# Buttons.net
KiCad netlist of a schematic drawn in Altium Designer
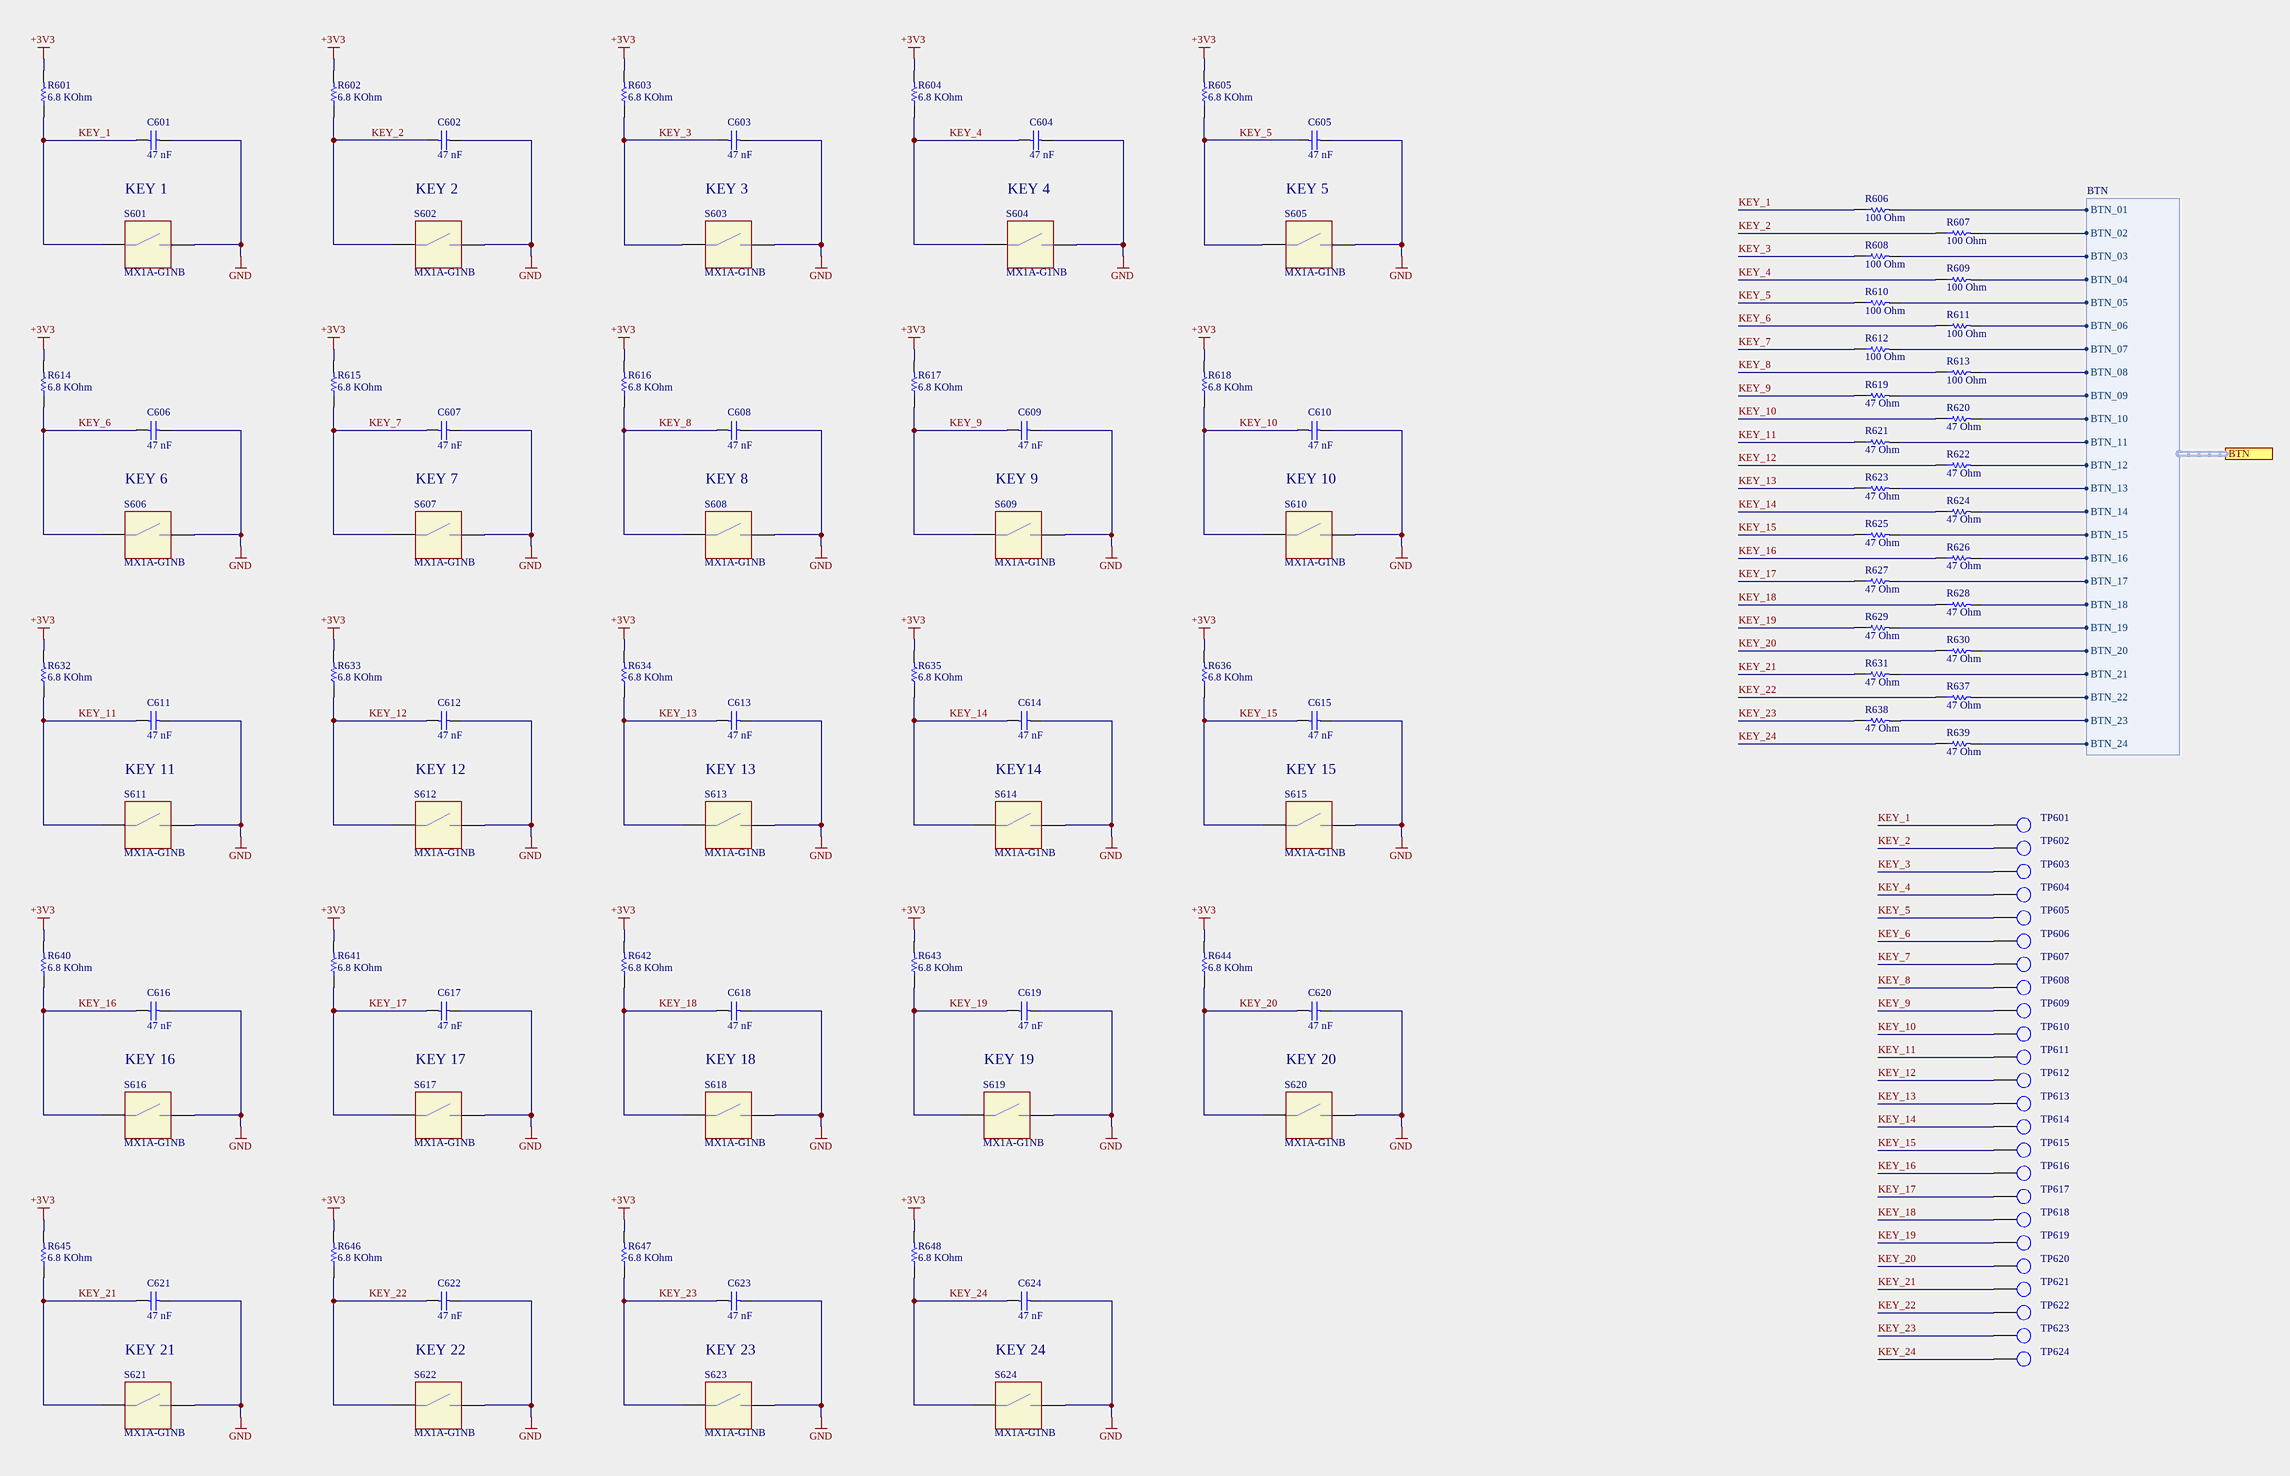
[diagram p0: Buttons.SchDoc]

(export (version "E")
  (design (tool "Eeschema 10.0.6"))
  (components
    (comp (ref "C601")
      (value "CAP-47N")
      (footprint "CAPC0603")
      (description "Chip Capacitor, 47 nF, +/- 5%")
      (fields (field (name "TOLERANCE") "5 %") (field (name "CAPACITANCE") "47 nF"))
      (libsource (lib "Конденсаторы керамические SMD") (part "CAP-47N"))
    )
    (comp (ref "C602")
      (value "CAP-47N")
      (footprint "CAPC0603")
      (description "Chip Capacitor, 47 nF, +/- 5%")
      (fields (field (name "TOLERANCE") "5 %") (field (name "CAPACITANCE") "47 nF"))
      (libsource (lib "Конденсаторы керамические SMD") (part "CAP-47N"))
    )
    (comp (ref "C603")
      (value "CAP-47N")
      (footprint "CAPC0603")
      (description "Chip Capacitor, 47 nF, +/- 5%")
      (fields (field (name "TOLERANCE") "5 %") (field (name "CAPACITANCE") "47 nF"))
      (libsource (lib "Конденсаторы керамические SMD") (part "CAP-47N"))
    )
    (comp (ref "C604")
      (value "CAP-47N")
      (footprint "CAPC0603")
      (description "Chip Capacitor, 47 nF, +/- 5%")
      (fields (field (name "TOLERANCE") "5 %") (field (name "CAPACITANCE") "47 nF"))
      (libsource (lib "Конденсаторы керамические SMD") (part "CAP-47N"))
    )
    (comp (ref "C605")
      (value "CAP-47N")
      (footprint "CAPC0603")
      (description "Chip Capacitor, 47 nF, +/- 5%")
      (fields (field (name "TOLERANCE") "5 %") (field (name "CAPACITANCE") "47 nF"))
      (libsource (lib "Конденсаторы керамические SMD") (part "CAP-47N"))
    )
    (comp (ref "C606")
      (value "CAP-47N")
      (footprint "CAPC0603")
      (description "Chip Capacitor, 47 nF, +/- 5%")
      (fields (field (name "TOLERANCE") "5 %") (field (name "CAPACITANCE") "47 nF"))
      (libsource (lib "Конденсаторы керамические SMD") (part "CAP-47N"))
    )
    (comp (ref "C607")
      (value "CAP-47N")
      (footprint "CAPC0603")
      (description "Chip Capacitor, 47 nF, +/- 5%")
      (fields (field (name "TOLERANCE") "5 %") (field (name "CAPACITANCE") "47 nF"))
      (libsource (lib "Конденсаторы керамические SMD") (part "CAP-47N"))
    )
    (comp (ref "C608")
      (value "CAP-47N")
      (footprint "CAPC0603")
      (description "Chip Capacitor, 47 nF, +/- 5%")
      (fields (field (name "TOLERANCE") "5 %") (field (name "CAPACITANCE") "47 nF"))
      (libsource (lib "Конденсаторы керамические SMD") (part "CAP-47N"))
    )
    (comp (ref "C609")
      (value "CAP-47N")
      (footprint "CAPC0603")
      (description "Chip Capacitor, 47 nF, +/- 5%")
      (fields (field (name "TOLERANCE") "5 %") (field (name "CAPACITANCE") "47 nF"))
      (libsource (lib "Конденсаторы керамические SMD") (part "CAP-47N"))
    )
    (comp (ref "C610")
      (value "CAP-47N")
      (footprint "CAPC0603")
      (description "Chip Capacitor, 47 nF, +/- 5%")
      (fields (field (name "TOLERANCE") "5 %") (field (name "CAPACITANCE") "47 nF"))
      (libsource (lib "Конденсаторы керамические SMD") (part "CAP-47N"))
    )
    (comp (ref "C611")
      (value "CAP-47N")
      (footprint "CAPC0603")
      (description "Chip Capacitor, 47 nF, +/- 5%")
      (fields (field (name "TOLERANCE") "5 %") (field (name "CAPACITANCE") "47 nF"))
      (libsource (lib "Конденсаторы керамические SMD") (part "CAP-47N"))
    )
    (comp (ref "C612")
      (value "CAP-47N")
      (footprint "CAPC0603")
      (description "Chip Capacitor, 47 nF, +/- 5%")
      (fields (field (name "TOLERANCE") "5 %") (field (name "CAPACITANCE") "47 nF"))
      (libsource (lib "Конденсаторы керамические SMD") (part "CAP-47N"))
    )
    (comp (ref "C613")
      (value "CAP-47N")
      (footprint "CAPC0603")
      (description "Chip Capacitor, 47 nF, +/- 5%")
      (fields (field (name "TOLERANCE") "5 %") (field (name "CAPACITANCE") "47 nF"))
      (libsource (lib "Конденсаторы керамические SMD") (part "CAP-47N"))
    )
    (comp (ref "C614")
      (value "CAP-47N")
      (footprint "CAPC0603")
      (description "Chip Capacitor, 47 nF, +/- 5%")
      (fields (field (name "TOLERANCE") "5 %") (field (name "CAPACITANCE") "47 nF"))
      (libsource (lib "Конденсаторы керамические SMD") (part "CAP-47N"))
    )
    (comp (ref "C615")
      (value "CAP-47N")
      (footprint "CAPC0603")
      (description "Chip Capacitor, 47 nF, +/- 5%")
      (fields (field (name "TOLERANCE") "5 %") (field (name "CAPACITANCE") "47 nF"))
      (libsource (lib "Конденсаторы керамические SMD") (part "CAP-47N"))
    )
    (comp (ref "C616")
      (value "CAP-47N")
      (footprint "CAPC0603")
      (description "Chip Capacitor, 47 nF, +/- 5%")
      (fields (field (name "TOLERANCE") "5 %") (field (name "CAPACITANCE") "47 nF"))
      (libsource (lib "Конденсаторы керамические SMD") (part "CAP-47N"))
    )
    (comp (ref "C617")
      (value "CAP-47N")
      (footprint "CAPC0603")
      (description "Chip Capacitor, 47 nF, +/- 5%")
      (fields (field (name "TOLERANCE") "5 %") (field (name "CAPACITANCE") "47 nF"))
      (libsource (lib "Конденсаторы керамические SMD") (part "CAP-47N"))
    )
    (comp (ref "C618")
      (value "CAP-47N")
      (footprint "CAPC0603")
      (description "Chip Capacitor, 47 nF, +/- 5%")
      (fields (field (name "TOLERANCE") "5 %") (field (name "CAPACITANCE") "47 nF"))
      (libsource (lib "Конденсаторы керамические SMD") (part "CAP-47N"))
    )
    (comp (ref "C619")
      (value "CAP-47N")
      (footprint "CAPC0603")
      (description "Chip Capacitor, 47 nF, +/- 5%")
      (fields (field (name "TOLERANCE") "5 %") (field (name "CAPACITANCE") "47 nF"))
      (libsource (lib "Конденсаторы керамические SMD") (part "CAP-47N"))
    )
    (comp (ref "C620")
      (value "CAP-47N")
      (footprint "CAPC0603")
      (description "Chip Capacitor, 47 nF, +/- 5%")
      (fields (field (name "TOLERANCE") "5 %") (field (name "CAPACITANCE") "47 nF"))
      (libsource (lib "Конденсаторы керамические SMD") (part "CAP-47N"))
    )
    (comp (ref "C621")
      (value "CAP-47N")
      (footprint "CAPC0603")
      (description "Chip Capacitor, 47 nF, +/- 5%")
      (fields (field (name "TOLERANCE") "5 %") (field (name "CAPACITANCE") "47 nF"))
      (libsource (lib "Конденсаторы керамические SMD") (part "CAP-47N"))
    )
    (comp (ref "C622")
      (value "CAP-47N")
      (footprint "CAPC0603")
      (description "Chip Capacitor, 47 nF, +/- 5%")
      (fields (field (name "TOLERANCE") "5 %") (field (name "CAPACITANCE") "47 nF"))
      (libsource (lib "Конденсаторы керамические SMD") (part "CAP-47N"))
    )
    (comp (ref "C623")
      (value "CAP-47N")
      (footprint "CAPC0603")
      (description "Chip Capacitor, 47 nF, +/- 5%")
      (fields (field (name "TOLERANCE") "5 %") (field (name "CAPACITANCE") "47 nF"))
      (libsource (lib "Конденсаторы керамические SMD") (part "CAP-47N"))
    )
    (comp (ref "C624")
      (value "CAP-47N")
      (footprint "CAPC0603")
      (description "Chip Capacitor, 47 nF, +/- 5%")
      (fields (field (name "TOLERANCE") "5 %") (field (name "CAPACITANCE") "47 nF"))
      (libsource (lib "Конденсаторы керамические SMD") (part "CAP-47N"))
    )
    (comp (ref "R601")
      (value "RES-6K8")
      (footprint "RES0603")
      (description "Chip Resistor, 6.8 KOhm, +/- 1%")
      (fields (field (name "TOLERANCE") "1 %") (field (name "RESISTANCE") "6.8 KOhm"))
      (libsource (lib "Резисторы SMD") (part "RES-6K8"))
    )
    (comp (ref "R602")
      (value "RES-6K8")
      (footprint "RES0603")
      (description "Chip Resistor, 6.8 KOhm, +/- 1%")
      (fields (field (name "TOLERANCE") "1 %") (field (name "RESISTANCE") "6.8 KOhm"))
      (libsource (lib "Резисторы SMD") (part "RES-6K8"))
    )
    (comp (ref "R603")
      (value "RES-6K8")
      (footprint "RES0603")
      (description "Chip Resistor, 6.8 KOhm, +/- 1%")
      (fields (field (name "TOLERANCE") "1 %") (field (name "RESISTANCE") "6.8 KOhm"))
      (libsource (lib "Резисторы SMD") (part "RES-6K8"))
    )
    (comp (ref "R604")
      (value "RES-6K8")
      (footprint "RES0603")
      (description "Chip Resistor, 6.8 KOhm, +/- 1%")
      (fields (field (name "TOLERANCE") "1 %") (field (name "RESISTANCE") "6.8 KOhm"))
      (libsource (lib "Резисторы SMD") (part "RES-6K8"))
    )
    (comp (ref "R605")
      (value "RES-6K8")
      (footprint "RES0603")
      (description "Chip Resistor, 6.8 KOhm, +/- 1%")
      (fields (field (name "TOLERANCE") "1 %") (field (name "RESISTANCE") "6.8 KOhm"))
      (libsource (lib "Резисторы SMD") (part "RES-6K8"))
    )
    (comp (ref "R606")
      (value "RES-100")
      (footprint "RES0603")
      (description "Chip Resistor, 100 Ohm, +/- 1%")
      (fields (field (name "TOLERANCE") "1 %") (field (name "RESISTANCE") "100 Ohm"))
      (libsource (lib "Резисторы SMD") (part "RES-100"))
    )
    (comp (ref "R607")
      (value "RES-100")
      (footprint "RES0603")
      (description "Chip Resistor, 100 Ohm, +/- 1%")
      (fields (field (name "TOLERANCE") "1 %") (field (name "RESISTANCE") "100 Ohm"))
      (libsource (lib "Резисторы SMD") (part "RES-100"))
    )
    (comp (ref "R608")
      (value "RES-100")
      (footprint "RES0603")
      (description "Chip Resistor, 100 Ohm, +/- 1%")
      (fields (field (name "TOLERANCE") "1 %") (field (name "RESISTANCE") "100 Ohm"))
      (libsource (lib "Резисторы SMD") (part "RES-100"))
    )
    (comp (ref "R609")
      (value "RES-100")
      (footprint "RES0603")
      (description "Chip Resistor, 100 Ohm, +/- 1%")
      (fields (field (name "TOLERANCE") "1 %") (field (name "RESISTANCE") "100 Ohm"))
      (libsource (lib "Резисторы SMD") (part "RES-100"))
    )
    (comp (ref "R610")
      (value "RES-100")
      (footprint "RES0603")
      (description "Chip Resistor, 100 Ohm, +/- 1%")
      (fields (field (name "TOLERANCE") "1 %") (field (name "RESISTANCE") "100 Ohm"))
      (libsource (lib "Резисторы SMD") (part "RES-100"))
    )
    (comp (ref "R611")
      (value "RES-100")
      (footprint "RES0603")
      (description "Chip Resistor, 100 Ohm, +/- 1%")
      (fields (field (name "TOLERANCE") "1 %") (field (name "RESISTANCE") "100 Ohm"))
      (libsource (lib "Резисторы SMD") (part "RES-100"))
    )
    (comp (ref "R612")
      (value "RES-100")
      (footprint "RES0603")
      (description "Chip Resistor, 100 Ohm, +/- 1%")
      (fields (field (name "TOLERANCE") "1 %") (field (name "RESISTANCE") "100 Ohm"))
      (libsource (lib "Резисторы SMD") (part "RES-100"))
    )
    (comp (ref "R613")
      (value "RES-100")
      (footprint "RES0603")
      (description "Chip Resistor, 100 Ohm, +/- 1%")
      (fields (field (name "TOLERANCE") "1 %") (field (name "RESISTANCE") "100 Ohm"))
      (libsource (lib "Резисторы SMD") (part "RES-100"))
    )
    (comp (ref "R614")
      (value "RES-6K8")
      (footprint "RES0603")
      (description "Chip Resistor, 6.8 KOhm, +/- 1%")
      (fields (field (name "TOLERANCE") "1 %") (field (name "RESISTANCE") "6.8 KOhm"))
      (libsource (lib "Резисторы SMD") (part "RES-6K8"))
    )
    (comp (ref "R615")
      (value "RES-6K8")
      (footprint "RES0603")
      (description "Chip Resistor, 6.8 KOhm, +/- 1%")
      (fields (field (name "TOLERANCE") "1 %") (field (name "RESISTANCE") "6.8 KOhm"))
      (libsource (lib "Резисторы SMD") (part "RES-6K8"))
    )
    (comp (ref "R616")
      (value "RES-6K8")
      (footprint "RES0603")
      (description "Chip Resistor, 6.8 KOhm, +/- 1%")
      (fields (field (name "TOLERANCE") "1 %") (field (name "RESISTANCE") "6.8 KOhm"))
      (libsource (lib "Резисторы SMD") (part "RES-6K8"))
    )
    (comp (ref "R617")
      (value "RES-6K8")
      (footprint "RES0603")
      (description "Chip Resistor, 6.8 KOhm, +/- 1%")
      (fields (field (name "TOLERANCE") "1 %") (field (name "RESISTANCE") "6.8 KOhm"))
      (libsource (lib "Резисторы SMD") (part "RES-6K8"))
    )
    (comp (ref "R618")
      (value "RES-6K8")
      (footprint "RES0603")
      (description "Chip Resistor, 6.8 KOhm, +/- 1%")
      (fields (field (name "TOLERANCE") "1 %") (field (name "RESISTANCE") "6.8 KOhm"))
      (libsource (lib "Резисторы SMD") (part "RES-6K8"))
    )
    (comp (ref "R619")
      (value "RES-47")
      (footprint "RES0603")
      (description "Chip Resistor, 47 Ohm, +/- 1%")
      (fields (field (name "TOLERANCE") "1 %") (field (name "RESISTANCE") "47 Ohm"))
      (libsource (lib "Резисторы SMD") (part "RES-47"))
    )
    (comp (ref "R620")
      (value "RES-47")
      (footprint "RES0603")
      (description "Chip Resistor, 47 Ohm, +/- 1%")
      (fields (field (name "TOLERANCE") "1 %") (field (name "RESISTANCE") "47 Ohm"))
      (libsource (lib "Резисторы SMD") (part "RES-47"))
    )
    (comp (ref "R621")
      (value "RES-47")
      (footprint "RES0603")
      (description "Chip Resistor, 47 Ohm, +/- 1%")
      (fields (field (name "TOLERANCE") "1 %") (field (name "RESISTANCE") "47 Ohm"))
      (libsource (lib "Резисторы SMD") (part "RES-47"))
    )
    (comp (ref "R622")
      (value "RES-47")
      (footprint "RES0603")
      (description "Chip Resistor, 47 Ohm, +/- 1%")
      (fields (field (name "TOLERANCE") "1 %") (field (name "RESISTANCE") "47 Ohm"))
      (libsource (lib "Резисторы SMD") (part "RES-47"))
    )
    (comp (ref "R623")
      (value "RES-47")
      (footprint "RES0603")
      (description "Chip Resistor, 47 Ohm, +/- 1%")
      (fields (field (name "TOLERANCE") "1 %") (field (name "RESISTANCE") "47 Ohm"))
      (libsource (lib "Резисторы SMD") (part "RES-47"))
    )
    (comp (ref "R624")
      (value "RES-47")
      (footprint "RES0603")
      (description "Chip Resistor, 47 Ohm, +/- 1%")
      (fields (field (name "TOLERANCE") "1 %") (field (name "RESISTANCE") "47 Ohm"))
      (libsource (lib "Резисторы SMD") (part "RES-47"))
    )
    (comp (ref "R625")
      (value "RES-47")
      (footprint "RES0603")
      (description "Chip Resistor, 47 Ohm, +/- 1%")
      (fields (field (name "TOLERANCE") "1 %") (field (name "RESISTANCE") "47 Ohm"))
      (libsource (lib "Резисторы SMD") (part "RES-47"))
    )
    (comp (ref "R626")
      (value "RES-47")
      (footprint "RES0603")
      (description "Chip Resistor, 47 Ohm, +/- 1%")
      (fields (field (name "TOLERANCE") "1 %") (field (name "RESISTANCE") "47 Ohm"))
      (libsource (lib "Резисторы SMD") (part "RES-47"))
    )
    (comp (ref "R627")
      (value "RES-47")
      (footprint "RES0603")
      (description "Chip Resistor, 47 Ohm, +/- 1%")
      (fields (field (name "TOLERANCE") "1 %") (field (name "RESISTANCE") "47 Ohm"))
      (libsource (lib "Резисторы SMD") (part "RES-47"))
    )
    (comp (ref "R628")
      (value "RES-47")
      (footprint "RES0603")
      (description "Chip Resistor, 47 Ohm, +/- 1%")
      (fields (field (name "TOLERANCE") "1 %") (field (name "RESISTANCE") "47 Ohm"))
      (libsource (lib "Резисторы SMD") (part "RES-47"))
    )
    (comp (ref "R629")
      (value "RES-47")
      (footprint "RES0603")
      (description "Chip Resistor, 47 Ohm, +/- 1%")
      (fields (field (name "TOLERANCE") "1 %") (field (name "RESISTANCE") "47 Ohm"))
      (libsource (lib "Резисторы SMD") (part "RES-47"))
    )
    (comp (ref "R630")
      (value "RES-47")
      (footprint "RES0603")
      (description "Chip Resistor, 47 Ohm, +/- 1%")
      (fields (field (name "TOLERANCE") "1 %") (field (name "RESISTANCE") "47 Ohm"))
      (libsource (lib "Резисторы SMD") (part "RES-47"))
    )
    (comp (ref "R631")
      (value "RES-47")
      (footprint "RES0603")
      (description "Chip Resistor, 47 Ohm, +/- 1%")
      (fields (field (name "TOLERANCE") "1 %") (field (name "RESISTANCE") "47 Ohm"))
      (libsource (lib "Резисторы SMD") (part "RES-47"))
    )
    (comp (ref "R632")
      (value "RES-6K8")
      (footprint "RES0603")
      (description "Chip Resistor, 6.8 KOhm, +/- 1%")
      (fields (field (name "TOLERANCE") "1 %") (field (name "RESISTANCE") "6.8 KOhm"))
      (libsource (lib "Резисторы SMD") (part "RES-6K8"))
    )
    (comp (ref "R633")
      (value "RES-6K8")
      (footprint "RES0603")
      (description "Chip Resistor, 6.8 KOhm, +/- 1%")
      (fields (field (name "TOLERANCE") "1 %") (field (name "RESISTANCE") "6.8 KOhm"))
      (libsource (lib "Резисторы SMD") (part "RES-6K8"))
    )
    (comp (ref "R634")
      (value "RES-6K8")
      (footprint "RES0603")
      (description "Chip Resistor, 6.8 KOhm, +/- 1%")
      (fields (field (name "TOLERANCE") "1 %") (field (name "RESISTANCE") "6.8 KOhm"))
      (libsource (lib "Резисторы SMD") (part "RES-6K8"))
    )
    (comp (ref "R635")
      (value "RES-6K8")
      (footprint "RES0603")
      (description "Chip Resistor, 6.8 KOhm, +/- 1%")
      (fields (field (name "TOLERANCE") "1 %") (field (name "RESISTANCE") "6.8 KOhm"))
      (libsource (lib "Резисторы SMD") (part "RES-6K8"))
    )
    (comp (ref "R636")
      (value "RES-6K8")
      (footprint "RES0603")
      (description "Chip Resistor, 6.8 KOhm, +/- 1%")
      (fields (field (name "TOLERANCE") "1 %") (field (name "RESISTANCE") "6.8 KOhm"))
      (libsource (lib "Резисторы SMD") (part "RES-6K8"))
    )
    (comp (ref "R637")
      (value "RES-47")
      (footprint "RES0603")
      (description "Chip Resistor, 47 Ohm, +/- 1%")
      (fields (field (name "TOLERANCE") "1 %") (field (name "RESISTANCE") "47 Ohm"))
      (libsource (lib "Резисторы SMD") (part "RES-47"))
    )
    (comp (ref "R638")
      (value "RES-47")
      (footprint "RES0603")
      (description "Chip Resistor, 47 Ohm, +/- 1%")
      (fields (field (name "TOLERANCE") "1 %") (field (name "RESISTANCE") "47 Ohm"))
      (libsource (lib "Резисторы SMD") (part "RES-47"))
    )
    (comp (ref "R639")
      (value "RES-47")
      (footprint "RES0603")
      (description "Chip Resistor, 47 Ohm, +/- 1%")
      (fields (field (name "TOLERANCE") "1 %") (field (name "RESISTANCE") "47 Ohm"))
      (libsource (lib "Резисторы SMD") (part "RES-47"))
    )
    (comp (ref "R640")
      (value "RES-6K8")
      (footprint "RES0603")
      (description "Chip Resistor, 6.8 KOhm, +/- 1%")
      (fields (field (name "TOLERANCE") "1 %") (field (name "RESISTANCE") "6.8 KOhm"))
      (libsource (lib "Резисторы SMD") (part "RES-6K8"))
    )
    (comp (ref "R641")
      (value "RES-6K8")
      (footprint "RES0603")
      (description "Chip Resistor, 6.8 KOhm, +/- 1%")
      (fields (field (name "TOLERANCE") "1 %") (field (name "RESISTANCE") "6.8 KOhm"))
      (libsource (lib "Резисторы SMD") (part "RES-6K8"))
    )
    (comp (ref "R642")
      (value "RES-6K8")
      (footprint "RES0603")
      (description "Chip Resistor, 6.8 KOhm, +/- 1%")
      (fields (field (name "TOLERANCE") "1 %") (field (name "RESISTANCE") "6.8 KOhm"))
      (libsource (lib "Резисторы SMD") (part "RES-6K8"))
    )
    (comp (ref "R643")
      (value "RES-6K8")
      (footprint "RES0603")
      (description "Chip Resistor, 6.8 KOhm, +/- 1%")
      (fields (field (name "TOLERANCE") "1 %") (field (name "RESISTANCE") "6.8 KOhm"))
      (libsource (lib "Резисторы SMD") (part "RES-6K8"))
    )
    (comp (ref "R644")
      (value "RES-6K8")
      (footprint "RES0603")
      (description "Chip Resistor, 6.8 KOhm, +/- 1%")
      (fields (field (name "TOLERANCE") "1 %") (field (name "RESISTANCE") "6.8 KOhm"))
      (libsource (lib "Резисторы SMD") (part "RES-6K8"))
    )
    (comp (ref "R645")
      (value "RES-6K8")
      (footprint "RES0603")
      (description "Chip Resistor, 6.8 KOhm, +/- 1%")
      (fields (field (name "TOLERANCE") "1 %") (field (name "RESISTANCE") "6.8 KOhm"))
      (libsource (lib "Резисторы SMD") (part "RES-6K8"))
    )
    (comp (ref "R646")
      (value "RES-6K8")
      (footprint "RES0603")
      (description "Chip Resistor, 6.8 KOhm, +/- 1%")
      (fields (field (name "TOLERANCE") "1 %") (field (name "RESISTANCE") "6.8 KOhm"))
      (libsource (lib "Резисторы SMD") (part "RES-6K8"))
    )
    (comp (ref "R647")
      (value "RES-6K8")
      (footprint "RES0603")
      (description "Chip Resistor, 6.8 KOhm, +/- 1%")
      (fields (field (name "TOLERANCE") "1 %") (field (name "RESISTANCE") "6.8 KOhm"))
      (libsource (lib "Резисторы SMD") (part "RES-6K8"))
    )
    (comp (ref "R648")
      (value "RES-6K8")
      (footprint "RES0603")
      (description "Chip Resistor, 6.8 KOhm, +/- 1%")
      (fields (field (name "TOLERANCE") "1 %") (field (name "RESISTANCE") "6.8 KOhm"))
      (libsource (lib "Резисторы SMD") (part "RES-6K8"))
    )
    (comp (ref "S601")
      (value "KEY 1")
      (footprint "CHERRY MX PCB WITHOUT LED")
      (description "CHERRY MX Brown RGB Keyswitch 55cN")
      (fields (field (name "MODEL") "MX1A-G1NB"))
      (libsource (lib "Кнопки") (part "MX1A-G1NB"))
    )
    (comp (ref "S602")
      (value "KEY 2")
      (footprint "CHERRY MX PCB WITHOUT LED")
      (description "CHERRY MX Brown RGB Keyswitch 55cN")
      (fields (field (name "MODEL") "MX1A-G1NB"))
      (libsource (lib "Кнопки") (part "MX1A-G1NB"))
    )
    (comp (ref "S603")
      (value "KEY 3")
      (footprint "CHERRY MX PCB WITHOUT LED")
      (description "CHERRY MX Brown RGB Keyswitch 55cN")
      (fields (field (name "MODEL") "MX1A-G1NB"))
      (libsource (lib "Кнопки") (part "MX1A-G1NB"))
    )
    (comp (ref "S604")
      (value "KEY 4")
      (footprint "CHERRY MX PCB WITHOUT LED")
      (description "CHERRY MX Brown RGB Keyswitch 55cN")
      (fields (field (name "MODEL") "MX1A-G1NB"))
      (libsource (lib "Кнопки") (part "MX1A-G1NB"))
    )
    (comp (ref "S605")
      (value "KEY 5")
      (footprint "CHERRY MX PCB WITHOUT LED")
      (description "CHERRY MX Brown RGB Keyswitch 55cN")
      (fields (field (name "MODEL") "MX1A-G1NB"))
      (libsource (lib "Кнопки") (part "MX1A-G1NB"))
    )
    (comp (ref "S606")
      (value "KEY 6")
      (footprint "CHERRY MX PCB WITHOUT LED")
      (description "CHERRY MX Brown RGB Keyswitch 55cN")
      (fields (field (name "MODEL") "MX1A-G1NB"))
      (libsource (lib "Кнопки") (part "MX1A-G1NB"))
    )
    (comp (ref "S607")
      (value "KEY 7")
      (footprint "CHERRY MX PCB WITHOUT LED")
      (description "CHERRY MX Brown RGB Keyswitch 55cN")
      (fields (field (name "MODEL") "MX1A-G1NB"))
      (libsource (lib "Кнопки") (part "MX1A-G1NB"))
    )
    (comp (ref "S608")
      (value "KEY 8")
      (footprint "CHERRY MX PCB WITHOUT LED")
      (description "CHERRY MX Brown RGB Keyswitch 55cN")
      (fields (field (name "MODEL") "MX1A-G1NB"))
      (libsource (lib "Кнопки") (part "MX1A-G1NB"))
    )
    (comp (ref "S609")
      (value "KEY 9")
      (footprint "CHERRY MX PCB WITHOUT LED")
      (description "CHERRY MX Brown RGB Keyswitch 55cN")
      (fields (field (name "MODEL") "MX1A-G1NB"))
      (libsource (lib "Кнопки") (part "MX1A-G1NB"))
    )
    (comp (ref "S610")
      (value "KEY 10")
      (footprint "CHERRY MX PCB WITHOUT LED")
      (description "CHERRY MX Brown RGB Keyswitch 55cN")
      (fields (field (name "MODEL") "MX1A-G1NB"))
      (libsource (lib "Кнопки") (part "MX1A-G1NB"))
    )
    (comp (ref "S611")
      (value "KEY 11")
      (footprint "CHERRY MX PCB WITHOUT LED")
      (description "CHERRY MX Brown RGB Keyswitch 55cN")
      (fields (field (name "MODEL") "MX1A-G1NB"))
      (libsource (lib "Кнопки") (part "MX1A-G1NB"))
    )
    (comp (ref "S612")
      (value "KEY 12")
      (footprint "CHERRY MX PCB WITHOUT LED")
      (description "CHERRY MX Brown RGB Keyswitch 55cN")
      (fields (field (name "MODEL") "MX1A-G1NB"))
      (libsource (lib "Кнопки") (part "MX1A-G1NB"))
    )
    (comp (ref "S613")
      (value "KEY 13")
      (footprint "CHERRY MX PCB WITHOUT LED")
      (description "CHERRY MX Brown RGB Keyswitch 55cN")
      (fields (field (name "MODEL") "MX1A-G1NB"))
      (libsource (lib "Кнопки") (part "MX1A-G1NB"))
    )
    (comp (ref "S614")
      (value "KEY14")
      (footprint "CHERRY MX PCB WITHOUT LED")
      (description "CHERRY MX Brown RGB Keyswitch 55cN")
      (fields (field (name "MODEL") "MX1A-G1NB"))
      (libsource (lib "Кнопки") (part "MX1A-G1NB"))
    )
    (comp (ref "S615")
      (value "KEY 15")
      (footprint "CHERRY MX PCB WITHOUT LED")
      (description "CHERRY MX Brown RGB Keyswitch 55cN")
      (fields (field (name "MODEL") "MX1A-G1NB"))
      (libsource (lib "Кнопки") (part "MX1A-G1NB"))
    )
    (comp (ref "S616")
      (value "KEY 16")
      (footprint "CHERRY MX PCB WITHOUT LED")
      (description "CHERRY MX Brown RGB Keyswitch 55cN")
      (fields (field (name "MODEL") "MX1A-G1NB"))
      (libsource (lib "Кнопки") (part "MX1A-G1NB"))
    )
    (comp (ref "S617")
      (value "KEY 17")
      (footprint "CHERRY MX PCB WITHOUT LED")
      (description "CHERRY MX Brown RGB Keyswitch 55cN")
      (fields (field (name "MODEL") "MX1A-G1NB"))
      (libsource (lib "Кнопки") (part "MX1A-G1NB"))
    )
    (comp (ref "S618")
      (value "KEY 18")
      (footprint "CHERRY MX PCB WITHOUT LED")
      (description "CHERRY MX Brown RGB Keyswitch 55cN")
      (fields (field (name "MODEL") "MX1A-G1NB"))
      (libsource (lib "Кнопки") (part "MX1A-G1NB"))
    )
    (comp (ref "S619")
      (value "KEY 19")
      (footprint "CHERRY MX PCB WITHOUT LED")
      (description "CHERRY MX Brown RGB Keyswitch 55cN")
      (fields (field (name "MODEL") "MX1A-G1NB"))
      (libsource (lib "Кнопки") (part "MX1A-G1NB"))
    )
    (comp (ref "S620")
      (value "KEY 20")
      (footprint "CHERRY MX PCB WITHOUT LED")
      (description "CHERRY MX Brown RGB Keyswitch 55cN")
      (fields (field (name "MODEL") "MX1A-G1NB"))
      (libsource (lib "Кнопки") (part "MX1A-G1NB"))
    )
    (comp (ref "S621")
      (value "KEY 21")
      (footprint "CHERRY MX PCB WITHOUT LED")
      (description "CHERRY MX Brown RGB Keyswitch 55cN")
      (fields (field (name "MODEL") "MX1A-G1NB"))
      (libsource (lib "Кнопки") (part "MX1A-G1NB"))
    )
    (comp (ref "S622")
      (value "KEY 22")
      (footprint "CHERRY MX PCB WITHOUT LED")
      (description "CHERRY MX Brown RGB Keyswitch 55cN")
      (fields (field (name "MODEL") "MX1A-G1NB"))
      (libsource (lib "Кнопки") (part "MX1A-G1NB"))
    )
    (comp (ref "S623")
      (value "KEY 23")
      (footprint "CHERRY MX PCB WITHOUT LED")
      (description "CHERRY MX Brown RGB Keyswitch 55cN")
      (fields (field (name "MODEL") "MX1A-G1NB"))
      (libsource (lib "Кнопки") (part "MX1A-G1NB"))
    )
    (comp (ref "S624")
      (value "KEY 24")
      (footprint "CHERRY MX PCB WITHOUT LED")
      (description "CHERRY MX Brown RGB Keyswitch 55cN")
      (fields (field (name "MODEL") "MX1A-G1NB"))
      (libsource (lib "Кнопки") (part "MX1A-G1NB"))
    )
    (comp (ref "TP601") (value "~") (footprint "TP_C-0.5mm") (libsource (lib "Разъемы") (part "TestPad")))
    (comp (ref "TP602") (value "~") (footprint "TP_C-0.5mm") (libsource (lib "Разъемы") (part "TestPad")))
    (comp (ref "TP603") (value "~") (footprint "TP_C-0.5mm") (libsource (lib "Разъемы") (part "TestPad")))
    (comp (ref "TP604") (value "~") (footprint "TP_C-0.5mm") (libsource (lib "Разъемы") (part "TestPad")))
    (comp (ref "TP605") (value "~") (footprint "TP_C-0.5mm") (libsource (lib "Разъемы") (part "TestPad")))
    (comp (ref "TP606") (value "~") (footprint "TP_C-0.5mm") (libsource (lib "Разъемы") (part "TestPad")))
    (comp (ref "TP607") (value "~") (footprint "TP_C-0.5mm") (libsource (lib "Разъемы") (part "TestPad")))
    (comp (ref "TP608") (value "~") (footprint "TP_C-0.5mm") (libsource (lib "Разъемы") (part "TestPad")))
    (comp (ref "TP609") (value "~") (footprint "TP_C-0.5mm") (libsource (lib "Разъемы") (part "TestPad")))
    (comp (ref "TP610") (value "~") (footprint "TP_C-0.5mm") (libsource (lib "Разъемы") (part "TestPad")))
    (comp (ref "TP611") (value "~") (footprint "TP_C-0.5mm") (libsource (lib "Разъемы") (part "TestPad")))
    (comp (ref "TP612") (value "~") (footprint "TP_C-0.5mm") (libsource (lib "Разъемы") (part "TestPad")))
    (comp (ref "TP613") (value "~") (footprint "TP_C-0.5mm") (libsource (lib "Разъемы") (part "TestPad")))
    (comp (ref "TP614") (value "~") (footprint "TP_C-0.5mm") (libsource (lib "Разъемы") (part "TestPad")))
    (comp (ref "TP615") (value "~") (footprint "TP_C-0.5mm") (libsource (lib "Разъемы") (part "TestPad")))
    (comp (ref "TP616") (value "~") (footprint "TP_C-0.5mm") (libsource (lib "Разъемы") (part "TestPad")))
    (comp (ref "TP617") (value "~") (footprint "TP_C-0.5mm") (libsource (lib "Разъемы") (part "TestPad")))
    (comp (ref "TP618") (value "~") (footprint "TP_C-0.5mm") (libsource (lib "Разъемы") (part "TestPad")))
    (comp (ref "TP619") (value "~") (footprint "TP_C-0.5mm") (libsource (lib "Разъемы") (part "TestPad")))
    (comp (ref "TP620") (value "~") (footprint "TP_C-0.5mm") (libsource (lib "Разъемы") (part "TestPad")))
    (comp (ref "TP621") (value "~") (footprint "TP_C-0.5mm") (libsource (lib "Разъемы") (part "TestPad")))
    (comp (ref "TP622") (value "~") (footprint "TP_C-0.5mm") (libsource (lib "Разъемы") (part "TestPad")))
    (comp (ref "TP623") (value "~") (footprint "TP_C-0.5mm") (libsource (lib "Разъемы") (part "TestPad")))
    (comp (ref "TP624") (value "~") (footprint "TP_C-0.5mm") (libsource (lib "Разъемы") (part "TestPad")))
  )
  (nets
    (net (code "2") (name "+3V3") (class "Default")
      (node (ref "R601") (pin "2") (pinfunction "2_2") (pintype "passive"))
      (node (ref "R602") (pin "2") (pinfunction "2_2") (pintype "passive"))
      (node (ref "R603") (pin "2") (pinfunction "2_2") (pintype "passive"))
      (node (ref "R604") (pin "2") (pinfunction "2_2") (pintype "passive"))
      (node (ref "R605") (pin "2") (pinfunction "2_2") (pintype "passive"))
      (node (ref "R614") (pin "2") (pinfunction "2_2") (pintype "passive"))
      (node (ref "R615") (pin "2") (pinfunction "2_2") (pintype "passive"))
      (node (ref "R616") (pin "2") (pinfunction "2_2") (pintype "passive"))
      (node (ref "R617") (pin "2") (pinfunction "2_2") (pintype "passive"))
      (node (ref "R618") (pin "2") (pinfunction "2_2") (pintype "passive"))
      (node (ref "R632") (pin "2") (pinfunction "2_2") (pintype "passive"))
      (node (ref "R633") (pin "2") (pinfunction "2_2") (pintype "passive"))
      (node (ref "R634") (pin "2") (pinfunction "2_2") (pintype "passive"))
      (node (ref "R635") (pin "2") (pinfunction "2_2") (pintype "passive"))
      (node (ref "R636") (pin "2") (pinfunction "2_2") (pintype "passive"))
      (node (ref "R640") (pin "2") (pinfunction "2_2") (pintype "passive"))
      (node (ref "R641") (pin "2") (pinfunction "2_2") (pintype "passive"))
      (node (ref "R642") (pin "2") (pinfunction "2_2") (pintype "passive"))
      (node (ref "R643") (pin "2") (pinfunction "2_2") (pintype "passive"))
      (node (ref "R644") (pin "2") (pinfunction "2_2") (pintype "passive"))
      (node (ref "R645") (pin "2") (pinfunction "2_2") (pintype "passive"))
      (node (ref "R646") (pin "2") (pinfunction "2_2") (pintype "passive"))
      (node (ref "R647") (pin "2") (pinfunction "2_2") (pintype "passive"))
      (node (ref "R648") (pin "2") (pinfunction "2_2") (pintype "passive"))
    )
    (net (code "3") (name "/BTN_01") (class "Default")
      (node (ref "R606") (pin "2") (pinfunction "2_2") (pintype "passive"))
    )
    (net (code "4") (name "/BTN_02") (class "Default")
      (node (ref "R607") (pin "2") (pinfunction "2_2") (pintype "passive"))
    )
    (net (code "5") (name "/BTN_03") (class "Default")
      (node (ref "R608") (pin "2") (pinfunction "2_2") (pintype "passive"))
    )
    (net (code "6") (name "/BTN_04") (class "Default")
      (node (ref "R609") (pin "2") (pinfunction "2_2") (pintype "passive"))
    )
    (net (code "7") (name "/BTN_05") (class "Default")
      (node (ref "R610") (pin "2") (pinfunction "2_2") (pintype "passive"))
    )
    (net (code "8") (name "/BTN_06") (class "Default")
      (node (ref "R611") (pin "2") (pinfunction "2_2") (pintype "passive"))
    )
    (net (code "9") (name "/BTN_07") (class "Default")
      (node (ref "R612") (pin "2") (pinfunction "2_2") (pintype "passive"))
    )
    (net (code "10") (name "/BTN_08") (class "Default")
      (node (ref "R613") (pin "2") (pinfunction "2_2") (pintype "passive"))
    )
    (net (code "11") (name "/BTN_09") (class "Default")
      (node (ref "R619") (pin "2") (pinfunction "2_2") (pintype "passive"))
    )
    (net (code "12") (name "/BTN_10") (class "Default")
      (node (ref "R620") (pin "2") (pinfunction "2_2") (pintype "passive"))
    )
    (net (code "13") (name "/BTN_11") (class "Default")
      (node (ref "R621") (pin "2") (pinfunction "2_2") (pintype "passive"))
    )
    (net (code "14") (name "/BTN_12") (class "Default")
      (node (ref "R622") (pin "2") (pinfunction "2_2") (pintype "passive"))
    )
    (net (code "15") (name "/BTN_13") (class "Default")
      (node (ref "R623") (pin "2") (pinfunction "2_2") (pintype "passive"))
    )
    (net (code "16") (name "/BTN_14") (class "Default")
      (node (ref "R624") (pin "2") (pinfunction "2_2") (pintype "passive"))
    )
    (net (code "17") (name "/BTN_15") (class "Default")
      (node (ref "R625") (pin "2") (pinfunction "2_2") (pintype "passive"))
    )
    (net (code "18") (name "/BTN_16") (class "Default")
      (node (ref "R626") (pin "2") (pinfunction "2_2") (pintype "passive"))
    )
    (net (code "19") (name "/BTN_17") (class "Default")
      (node (ref "R627") (pin "2") (pinfunction "2_2") (pintype "passive"))
    )
    (net (code "20") (name "/BTN_18") (class "Default")
      (node (ref "R628") (pin "2") (pinfunction "2_2") (pintype "passive"))
    )
    (net (code "21") (name "/BTN_19") (class "Default")
      (node (ref "R629") (pin "2") (pinfunction "2_2") (pintype "passive"))
    )
    (net (code "22") (name "/BTN_20") (class "Default")
      (node (ref "R630") (pin "2") (pinfunction "2_2") (pintype "passive"))
    )
    (net (code "23") (name "/BTN_21") (class "Default")
      (node (ref "R631") (pin "2") (pinfunction "2_2") (pintype "passive"))
    )
    (net (code "24") (name "/BTN_22") (class "Default")
      (node (ref "R637") (pin "2") (pinfunction "2_2") (pintype "passive"))
    )
    (net (code "25") (name "/BTN_23") (class "Default")
      (node (ref "R638") (pin "2") (pinfunction "2_2") (pintype "passive"))
    )
    (net (code "26") (name "/BTN_24") (class "Default")
      (node (ref "R639") (pin "2") (pinfunction "2_2") (pintype "passive"))
    )
    (net (code "27") (name "/KEY_1") (class "Default")
      (node (ref "C601") (pin "1") (pinfunction "1_1") (pintype "passive"))
      (node (ref "R601") (pin "1") (pinfunction "1_1") (pintype "passive"))
      (node (ref "R606") (pin "1") (pinfunction "1_1") (pintype "passive"))
      (node (ref "S601") (pin "S1") (pintype "passive"))
      (node (ref "TP601") (pin "1") (pintype "passive"))
    )
    (net (code "28") (name "/KEY_2") (class "Default")
      (node (ref "C602") (pin "1") (pinfunction "1_1") (pintype "passive"))
      (node (ref "R602") (pin "1") (pinfunction "1_1") (pintype "passive"))
      (node (ref "R607") (pin "1") (pinfunction "1_1") (pintype "passive"))
      (node (ref "S602") (pin "S1") (pintype "passive"))
      (node (ref "TP602") (pin "1") (pintype "passive"))
    )
    (net (code "29") (name "/KEY_3") (class "Default")
      (node (ref "C603") (pin "1") (pinfunction "1_1") (pintype "passive"))
      (node (ref "R603") (pin "1") (pinfunction "1_1") (pintype "passive"))
      (node (ref "R608") (pin "1") (pinfunction "1_1") (pintype "passive"))
      (node (ref "S603") (pin "S1") (pintype "passive"))
      (node (ref "TP603") (pin "1") (pintype "passive"))
    )
    (net (code "30") (name "/KEY_4") (class "Default")
      (node (ref "C604") (pin "1") (pinfunction "1_1") (pintype "passive"))
      (node (ref "R604") (pin "1") (pinfunction "1_1") (pintype "passive"))
      (node (ref "R609") (pin "1") (pinfunction "1_1") (pintype "passive"))
      (node (ref "S604") (pin "S1") (pintype "passive"))
      (node (ref "TP604") (pin "1") (pintype "passive"))
    )
    (net (code "31") (name "/KEY_5") (class "Default")
      (node (ref "C605") (pin "1") (pinfunction "1_1") (pintype "passive"))
      (node (ref "R605") (pin "1") (pinfunction "1_1") (pintype "passive"))
      (node (ref "R610") (pin "1") (pinfunction "1_1") (pintype "passive"))
      (node (ref "S605") (pin "S1") (pintype "passive"))
      (node (ref "TP605") (pin "1") (pintype "passive"))
    )
    (net (code "32") (name "/KEY_6") (class "Default")
      (node (ref "C606") (pin "1") (pinfunction "1_1") (pintype "passive"))
      (node (ref "R611") (pin "1") (pinfunction "1_1") (pintype "passive"))
      (node (ref "R614") (pin "1") (pinfunction "1_1") (pintype "passive"))
      (node (ref "S606") (pin "S1") (pintype "passive"))
      (node (ref "TP606") (pin "1") (pintype "passive"))
    )
    (net (code "33") (name "/KEY_7") (class "Default")
      (node (ref "C607") (pin "1") (pinfunction "1_1") (pintype "passive"))
      (node (ref "R612") (pin "1") (pinfunction "1_1") (pintype "passive"))
      (node (ref "R615") (pin "1") (pinfunction "1_1") (pintype "passive"))
      (node (ref "S607") (pin "S1") (pintype "passive"))
      (node (ref "TP607") (pin "1") (pintype "passive"))
    )
    (net (code "34") (name "/KEY_8") (class "Default")
      (node (ref "C608") (pin "1") (pinfunction "1_1") (pintype "passive"))
      (node (ref "R613") (pin "1") (pinfunction "1_1") (pintype "passive"))
      (node (ref "R616") (pin "1") (pinfunction "1_1") (pintype "passive"))
      (node (ref "S608") (pin "S1") (pintype "passive"))
      (node (ref "TP608") (pin "1") (pintype "passive"))
    )
    (net (code "35") (name "/KEY_9") (class "Default")
      (node (ref "C609") (pin "1") (pinfunction "1_1") (pintype "passive"))
      (node (ref "R617") (pin "1") (pinfunction "1_1") (pintype "passive"))
      (node (ref "R619") (pin "1") (pinfunction "1_1") (pintype "passive"))
      (node (ref "S609") (pin "S1") (pintype "passive"))
      (node (ref "TP609") (pin "1") (pintype "passive"))
    )
    (net (code "36") (name "/KEY_10") (class "Default")
      (node (ref "C610") (pin "1") (pinfunction "1_1") (pintype "passive"))
      (node (ref "R618") (pin "1") (pinfunction "1_1") (pintype "passive"))
      (node (ref "R620") (pin "1") (pinfunction "1_1") (pintype "passive"))
      (node (ref "S610") (pin "S1") (pintype "passive"))
      (node (ref "TP610") (pin "1") (pintype "passive"))
    )
    (net (code "37") (name "/KEY_11") (class "Default")
      (node (ref "C611") (pin "1") (pinfunction "1_1") (pintype "passive"))
      (node (ref "R621") (pin "1") (pinfunction "1_1") (pintype "passive"))
      (node (ref "R632") (pin "1") (pinfunction "1_1") (pintype "passive"))
      (node (ref "S611") (pin "S1") (pintype "passive"))
      (node (ref "TP611") (pin "1") (pintype "passive"))
    )
    (net (code "38") (name "/KEY_12") (class "Default")
      (node (ref "C612") (pin "1") (pinfunction "1_1") (pintype "passive"))
      (node (ref "R622") (pin "1") (pinfunction "1_1") (pintype "passive"))
      (node (ref "R633") (pin "1") (pinfunction "1_1") (pintype "passive"))
      (node (ref "S612") (pin "S1") (pintype "passive"))
      (node (ref "TP612") (pin "1") (pintype "passive"))
    )
    (net (code "39") (name "/KEY_13") (class "Default")
      (node (ref "C613") (pin "1") (pinfunction "1_1") (pintype "passive"))
      (node (ref "R623") (pin "1") (pinfunction "1_1") (pintype "passive"))
      (node (ref "R634") (pin "1") (pinfunction "1_1") (pintype "passive"))
      (node (ref "S613") (pin "S1") (pintype "passive"))
      (node (ref "TP613") (pin "1") (pintype "passive"))
    )
    (net (code "40") (name "/KEY_14") (class "Default")
      (node (ref "C614") (pin "1") (pinfunction "1_1") (pintype "passive"))
      (node (ref "R624") (pin "1") (pinfunction "1_1") (pintype "passive"))
      (node (ref "R635") (pin "1") (pinfunction "1_1") (pintype "passive"))
      (node (ref "S614") (pin "S1") (pintype "passive"))
      (node (ref "TP614") (pin "1") (pintype "passive"))
    )
    (net (code "41") (name "/KEY_15") (class "Default")
      (node (ref "C615") (pin "1") (pinfunction "1_1") (pintype "passive"))
      (node (ref "R625") (pin "1") (pinfunction "1_1") (pintype "passive"))
      (node (ref "R636") (pin "1") (pinfunction "1_1") (pintype "passive"))
      (node (ref "S615") (pin "S1") (pintype "passive"))
      (node (ref "TP615") (pin "1") (pintype "passive"))
    )
    (net (code "42") (name "/KEY_16") (class "Default")
      (node (ref "C616") (pin "1") (pinfunction "1_1") (pintype "passive"))
      (node (ref "R626") (pin "1") (pinfunction "1_1") (pintype "passive"))
      (node (ref "R640") (pin "1") (pinfunction "1_1") (pintype "passive"))
      (node (ref "S616") (pin "S1") (pintype "passive"))
      (node (ref "TP616") (pin "1") (pintype "passive"))
    )
    (net (code "43") (name "/KEY_17") (class "Default")
      (node (ref "C617") (pin "1") (pinfunction "1_1") (pintype "passive"))
      (node (ref "R627") (pin "1") (pinfunction "1_1") (pintype "passive"))
      (node (ref "R641") (pin "1") (pinfunction "1_1") (pintype "passive"))
      (node (ref "S617") (pin "S1") (pintype "passive"))
      (node (ref "TP617") (pin "1") (pintype "passive"))
    )
    (net (code "44") (name "/KEY_18") (class "Default")
      (node (ref "C618") (pin "1") (pinfunction "1_1") (pintype "passive"))
      (node (ref "R628") (pin "1") (pinfunction "1_1") (pintype "passive"))
      (node (ref "R642") (pin "1") (pinfunction "1_1") (pintype "passive"))
      (node (ref "S618") (pin "S1") (pintype "passive"))
      (node (ref "TP618") (pin "1") (pintype "passive"))
    )
    (net (code "45") (name "/KEY_19") (class "Default")
      (node (ref "C619") (pin "1") (pinfunction "1_1") (pintype "passive"))
      (node (ref "R629") (pin "1") (pinfunction "1_1") (pintype "passive"))
      (node (ref "R643") (pin "1") (pinfunction "1_1") (pintype "passive"))
      (node (ref "S619") (pin "S1") (pintype "passive"))
      (node (ref "TP619") (pin "1") (pintype "passive"))
    )
    (net (code "46") (name "/KEY_20") (class "Default")
      (node (ref "C620") (pin "1") (pinfunction "1_1") (pintype "passive"))
      (node (ref "R630") (pin "1") (pinfunction "1_1") (pintype "passive"))
      (node (ref "R644") (pin "1") (pinfunction "1_1") (pintype "passive"))
      (node (ref "S620") (pin "S1") (pintype "passive"))
      (node (ref "TP620") (pin "1") (pintype "passive"))
    )
    (net (code "47") (name "/KEY_21") (class "Default")
      (node (ref "C621") (pin "1") (pinfunction "1_1") (pintype "passive"))
      (node (ref "R631") (pin "1") (pinfunction "1_1") (pintype "passive"))
      (node (ref "R645") (pin "1") (pinfunction "1_1") (pintype "passive"))
      (node (ref "S621") (pin "S1") (pintype "passive"))
      (node (ref "TP621") (pin "1") (pintype "passive"))
    )
    (net (code "48") (name "/KEY_22") (class "Default")
      (node (ref "C622") (pin "1") (pinfunction "1_1") (pintype "passive"))
      (node (ref "R637") (pin "1") (pinfunction "1_1") (pintype "passive"))
      (node (ref "R646") (pin "1") (pinfunction "1_1") (pintype "passive"))
      (node (ref "S622") (pin "S1") (pintype "passive"))
      (node (ref "TP622") (pin "1") (pintype "passive"))
    )
    (net (code "49") (name "/KEY_23") (class "Default")
      (node (ref "C623") (pin "1") (pinfunction "1_1") (pintype "passive"))
      (node (ref "R638") (pin "1") (pinfunction "1_1") (pintype "passive"))
      (node (ref "R647") (pin "1") (pinfunction "1_1") (pintype "passive"))
      (node (ref "S623") (pin "S1") (pintype "passive"))
      (node (ref "TP623") (pin "1") (pintype "passive"))
    )
    (net (code "50") (name "/KEY_24") (class "Default")
      (node (ref "C624") (pin "1") (pinfunction "1_1") (pintype "passive"))
      (node (ref "R639") (pin "1") (pinfunction "1_1") (pintype "passive"))
      (node (ref "R648") (pin "1") (pinfunction "1_1") (pintype "passive"))
      (node (ref "S624") (pin "S1") (pintype "passive"))
      (node (ref "TP624") (pin "1") (pintype "passive"))
    )
    (net (code "52") (name "GND") (class "Default")
      (node (ref "C601") (pin "2") (pinfunction "2_2") (pintype "passive"))
      (node (ref "C602") (pin "2") (pinfunction "2_2") (pintype "passive"))
      (node (ref "C603") (pin "2") (pinfunction "2_2") (pintype "passive"))
      (node (ref "C604") (pin "2") (pinfunction "2_2") (pintype "passive"))
      (node (ref "C605") (pin "2") (pinfunction "2_2") (pintype "passive"))
      (node (ref "C606") (pin "2") (pinfunction "2_2") (pintype "passive"))
      (node (ref "C607") (pin "2") (pinfunction "2_2") (pintype "passive"))
      (node (ref "C608") (pin "2") (pinfunction "2_2") (pintype "passive"))
      (node (ref "C609") (pin "2") (pinfunction "2_2") (pintype "passive"))
      (node (ref "C610") (pin "2") (pinfunction "2_2") (pintype "passive"))
      (node (ref "C611") (pin "2") (pinfunction "2_2") (pintype "passive"))
      (node (ref "C612") (pin "2") (pinfunction "2_2") (pintype "passive"))
      (node (ref "C613") (pin "2") (pinfunction "2_2") (pintype "passive"))
      (node (ref "C614") (pin "2") (pinfunction "2_2") (pintype "passive"))
      (node (ref "C615") (pin "2") (pinfunction "2_2") (pintype "passive"))
      (node (ref "C616") (pin "2") (pinfunction "2_2") (pintype "passive"))
      (node (ref "C617") (pin "2") (pinfunction "2_2") (pintype "passive"))
      (node (ref "C618") (pin "2") (pinfunction "2_2") (pintype "passive"))
      (node (ref "C619") (pin "2") (pinfunction "2_2") (pintype "passive"))
      (node (ref "C620") (pin "2") (pinfunction "2_2") (pintype "passive"))
      (node (ref "C621") (pin "2") (pinfunction "2_2") (pintype "passive"))
      (node (ref "C622") (pin "2") (pinfunction "2_2") (pintype "passive"))
      (node (ref "C623") (pin "2") (pinfunction "2_2") (pintype "passive"))
      (node (ref "C624") (pin "2") (pinfunction "2_2") (pintype "passive"))
      (node (ref "S601") (pin "S2") (pintype "passive"))
      (node (ref "S602") (pin "S2") (pintype "passive"))
      (node (ref "S603") (pin "S2") (pintype "passive"))
      (node (ref "S604") (pin "S2") (pintype "passive"))
      (node (ref "S605") (pin "S2") (pintype "passive"))
      (node (ref "S606") (pin "S2") (pintype "passive"))
      (node (ref "S607") (pin "S2") (pintype "passive"))
      (node (ref "S608") (pin "S2") (pintype "passive"))
      (node (ref "S609") (pin "S2") (pintype "passive"))
      (node (ref "S610") (pin "S2") (pintype "passive"))
      (node (ref "S611") (pin "S2") (pintype "passive"))
      (node (ref "S612") (pin "S2") (pintype "passive"))
      (node (ref "S613") (pin "S2") (pintype "passive"))
      (node (ref "S614") (pin "S2") (pintype "passive"))
      (node (ref "S615") (pin "S2") (pintype "passive"))
      (node (ref "S616") (pin "S2") (pintype "passive"))
      (node (ref "S617") (pin "S2") (pintype "passive"))
      (node (ref "S618") (pin "S2") (pintype "passive"))
      (node (ref "S619") (pin "S2") (pintype "passive"))
      (node (ref "S620") (pin "S2") (pintype "passive"))
      (node (ref "S621") (pin "S2") (pintype "passive"))
      (node (ref "S622") (pin "S2") (pintype "passive"))
      (node (ref "S623") (pin "S2") (pintype "passive"))
      (node (ref "S624") (pin "S2") (pintype "passive"))
    )
  )
)
